# har_DAA_FPGA_Programming.net
KiCad netlist of a schematic drawn in EAGLE
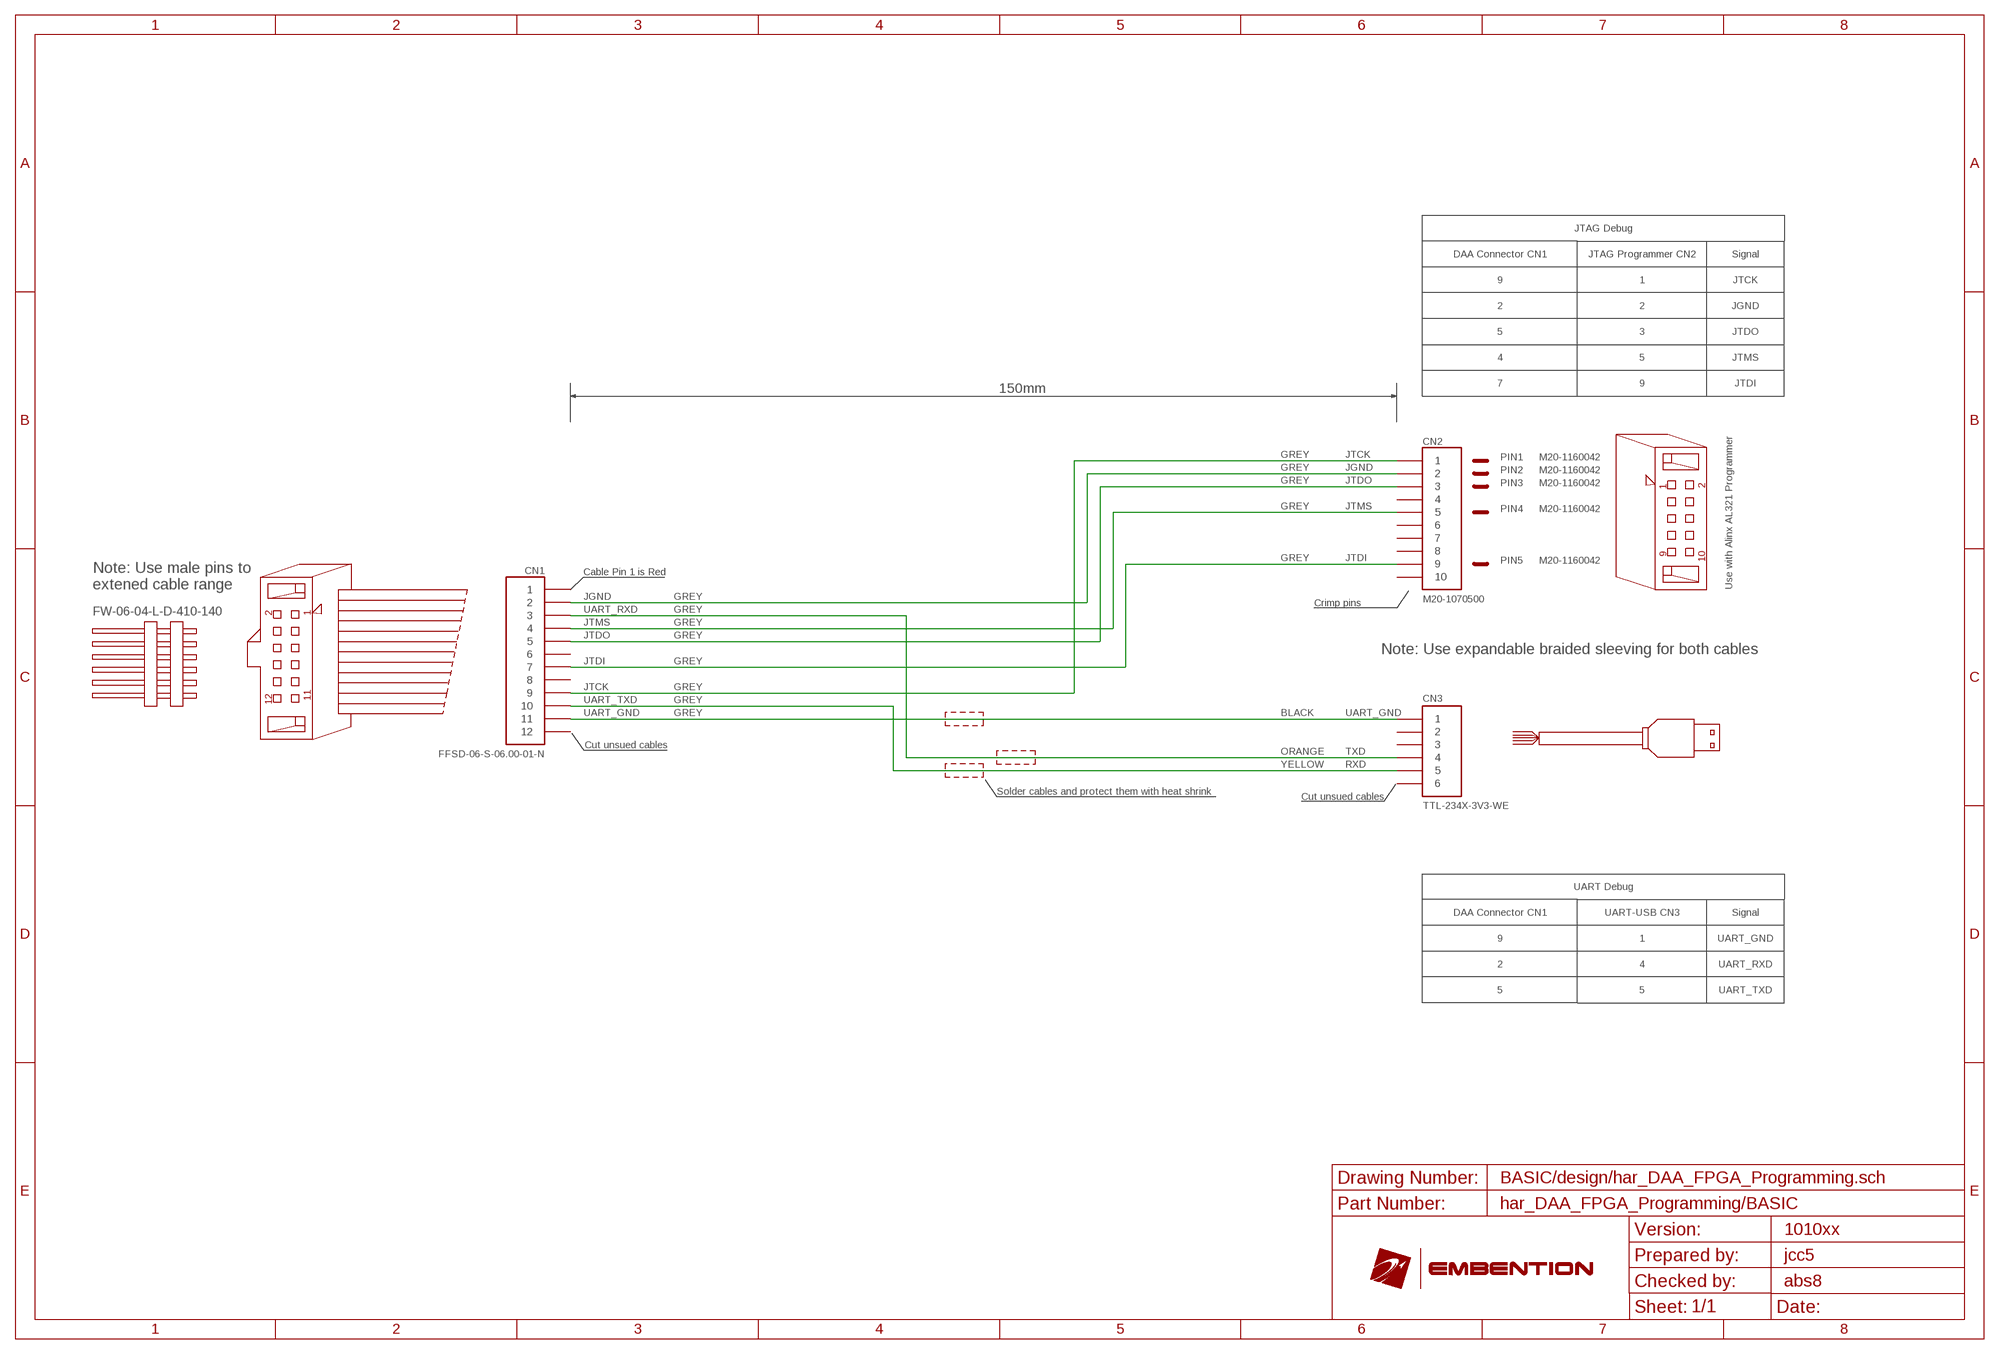
[diagram p0: schematic, sheet 1]

(export (version "E")
  (design (tool "Eeschema 10.0.6"))
  (components
    (comp (ref "CN1")
      (value "FFSD-06-S-06.00-01-N")
      (footprint "eagle-import:25-PIN")
      (libsource (lib "eagle-import") (part "12-PIN-NUM"))
    )
    (comp (ref "CN2")
      (value "M20-1070500")
      (footprint "eagle-import:25-PIN")
      (libsource (lib "eagle-import") (part "10-PIN-NUM"))
    )
    (comp (ref "CN3")
      (value "TTL-234X-3V3-WE")
      (footprint "eagle-import:25-PIN")
      (libsource (lib "eagle-import") (part "6-PIN-NUM"))
    )
    (comp (ref "CN4")
      (value "FW-06-04-L-D-410-140")
      (footprint "eagle-import:CLAMP")
      (libsource (lib "eagle-import") (part "0-PIN"))
    )
    (comp (ref "PIN1")
      (value "M20-1160042")
      (footprint "eagle-import:1-PIN")
      (libsource (lib "eagle-import") (part "CONN-PIN"))
    )
    (comp (ref "PIN2")
      (value "M20-1160042")
      (footprint "eagle-import:1-PIN")
      (libsource (lib "eagle-import") (part "CONN-PIN"))
    )
    (comp (ref "PIN3")
      (value "M20-1160042")
      (footprint "eagle-import:1-PIN")
      (libsource (lib "eagle-import") (part "CONN-PIN"))
    )
    (comp (ref "PIN4")
      (value "M20-1160042")
      (footprint "eagle-import:1-PIN")
      (libsource (lib "eagle-import") (part "CONN-PIN"))
    )
    (comp (ref "PIN5")
      (value "M20-1160042")
      (footprint "eagle-import:1-PIN")
      (libsource (lib "eagle-import") (part "CONN-PIN"))
    )
  )
  (nets
    (net (code "1") (name "/JGND") (class "Default")
      (node (ref "CN1") (pin "P$2") (pinfunction "2_P$2") (pintype "bidirectional"))
      (node (ref "CN2") (pin "P$2") (pinfunction "2_P$2") (pintype "bidirectional"))
    )
    (net (code "2") (name "/JTCK") (class "Default")
      (node (ref "CN1") (pin "P$9") (pinfunction "9_P$9") (pintype "bidirectional"))
      (node (ref "CN2") (pin "P$1") (pinfunction "1_P$1") (pintype "bidirectional"))
    )
    (net (code "3") (name "/JTDI") (class "Default")
      (node (ref "CN1") (pin "P$7") (pinfunction "7_P$7") (pintype "bidirectional"))
      (node (ref "CN2") (pin "P$9") (pinfunction "9_P$9") (pintype "bidirectional"))
    )
    (net (code "4") (name "/JTDO") (class "Default")
      (node (ref "CN1") (pin "P$5") (pinfunction "5_P$5") (pintype "bidirectional"))
      (node (ref "CN2") (pin "P$3") (pinfunction "3_P$3") (pintype "bidirectional"))
    )
    (net (code "5") (name "/JTMS") (class "Default")
      (node (ref "CN1") (pin "P$4") (pinfunction "4_P$4") (pintype "bidirectional"))
      (node (ref "CN2") (pin "P$5") (pinfunction "5_P$5") (pintype "bidirectional"))
    )
    (net (code "6") (name "/UART_GND") (class "Default")
      (node (ref "CN1") (pin "P$11") (pinfunction "11_P$11") (pintype "bidirectional"))
      (node (ref "CN3") (pin "P$1") (pinfunction "1_P$1") (pintype "bidirectional"))
    )
    (net (code "7") (name "/UART_RXD") (class "Default")
      (node (ref "CN1") (pin "P$3") (pinfunction "3_P$3") (pintype "bidirectional"))
      (node (ref "CN3") (pin "P$4") (pinfunction "4_P$4") (pintype "bidirectional"))
    )
    (net (code "8") (name "/UART_TXD") (class "Default")
      (node (ref "CN1") (pin "P$10") (pinfunction "10_P$10") (pintype "bidirectional"))
      (node (ref "CN3") (pin "P$5") (pinfunction "5_P$5") (pintype "bidirectional"))
    )
    (net (code "9") (name "unconnected-(CN1-1-PadP$1)") (class "Default")
      (node (ref "CN1") (pin "P$1") (pinfunction "1_P$1") (pintype "bidirectional"))
    )
    (net (code "10") (name "unconnected-(CN1-6-PadP$6)") (class "Default")
      (node (ref "CN1") (pin "P$6") (pinfunction "6_P$6") (pintype "bidirectional"))
    )
    (net (code "11") (name "unconnected-(CN1-8-PadP$8)") (class "Default")
      (node (ref "CN1") (pin "P$8") (pinfunction "8_P$8") (pintype "bidirectional"))
    )
    (net (code "12") (name "unconnected-(CN1-12-PadP$12)") (class "Default")
      (node (ref "CN1") (pin "P$12") (pinfunction "12_P$12") (pintype "bidirectional"))
    )
    (net (code "13") (name "unconnected-(CN2-4-PadP$4)") (class "Default")
      (node (ref "CN2") (pin "P$4") (pinfunction "4_P$4") (pintype "bidirectional"))
    )
    (net (code "14") (name "unconnected-(CN2-6-PadP$6)") (class "Default")
      (node (ref "CN2") (pin "P$6") (pinfunction "6_P$6") (pintype "bidirectional"))
    )
    (net (code "15") (name "unconnected-(CN2-7-PadP$7)") (class "Default")
      (node (ref "CN2") (pin "P$7") (pinfunction "7_P$7") (pintype "bidirectional"))
    )
    (net (code "16") (name "unconnected-(CN2-8-PadP$8)") (class "Default")
      (node (ref "CN2") (pin "P$8") (pinfunction "8_P$8") (pintype "bidirectional"))
    )
    (net (code "17") (name "unconnected-(CN2-10-PadP$10)") (class "Default")
      (node (ref "CN2") (pin "P$10") (pinfunction "10_P$10") (pintype "bidirectional"))
    )
    (net (code "18") (name "unconnected-(CN3-2-PadP$2)") (class "Default")
      (node (ref "CN3") (pin "P$2") (pinfunction "2_P$2") (pintype "bidirectional"))
    )
    (net (code "19") (name "unconnected-(CN3-3-PadP$3)") (class "Default")
      (node (ref "CN3") (pin "P$3") (pinfunction "3_P$3") (pintype "bidirectional"))
    )
    (net (code "20") (name "unconnected-(CN3-6-PadP$6)") (class "Default")
      (node (ref "CN3") (pin "P$6") (pinfunction "6_P$6") (pintype "bidirectional"))
    )
    (net (code "21") (name "unconnected-(PIN1-PadP$1)") (class "Default")
      (node (ref "PIN1") (pin "P$1") (pinfunction "P$1_P$1") (pintype "bidirectional"))
    )
    (net (code "22") (name "unconnected-(PIN2-PadP$1)") (class "Default")
      (node (ref "PIN2") (pin "P$1") (pinfunction "P$1_P$1") (pintype "bidirectional"))
    )
    (net (code "23") (name "unconnected-(PIN3-PadP$1)") (class "Default")
      (node (ref "PIN3") (pin "P$1") (pinfunction "P$1_P$1") (pintype "bidirectional"))
    )
    (net (code "24") (name "unconnected-(PIN4-PadP$1)") (class "Default")
      (node (ref "PIN4") (pin "P$1") (pinfunction "P$1_P$1") (pintype "bidirectional"))
    )
    (net (code "25") (name "unconnected-(PIN5-PadP$1)") (class "Default")
      (node (ref "PIN5") (pin "P$1") (pinfunction "P$1_P$1") (pintype "bidirectional"))
    )
  )
)
